# PULLDNx3.net
KiCad netlist of a schematic drawn in Altium Designer
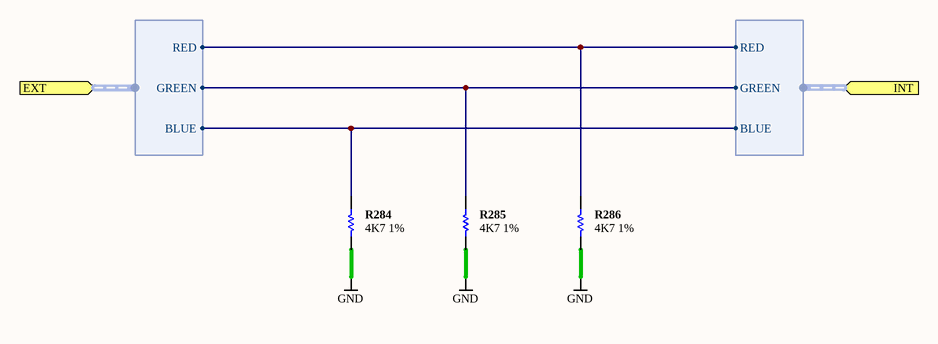
[diagram p0: PULLDNx3.SCHDOC]

(export (version "E")
  (design (tool "Eeschema 10.0.6"))
  (components
    (comp (ref "R284")
      (value "4K7 1%")
      (footprint "RESC1005-STAR")
      (description "Resistor, 4K7 1% 0402 (1005)")
      (fields (field (name "TOLERANCE") "1 %"))
      (libsource (lib "altium-import") (part "root_2_mirrored_RES_"))
    )
    (comp (ref "R285")
      (value "4K7 1%")
      (footprint "RESC1005-STAR")
      (description "Resistor, 4K7 1% 0402 (1005)")
      (fields (field (name "TOLERANCE") "1 %"))
      (libsource (lib "altium-import") (part "root_2_mirrored_RES_"))
    )
    (comp (ref "R286")
      (value "4K7 1%")
      (footprint "RESC1005-STAR")
      (description "Resistor, 4K7 1% 0402 (1005)")
      (fields (field (name "TOLERANCE") "1 %"))
      (libsource (lib "altium-import") (part "root_2_mirrored_RES_"))
    )
  )
  (nets
    (net (code "2") (name "/BLUE") (class "Default")
      (node (ref "R284") (pin "2") (pinfunction "2_2") (pintype "passive"))
    )
    (net (code "3") (name "/GREEN") (class "Default")
      (node (ref "R285") (pin "2") (pinfunction "2_2") (pintype "passive"))
    )
    (net (code "4") (name "/RED") (class "Default")
      (node (ref "R286") (pin "2") (pinfunction "2_2") (pintype "passive"))
    )
    (net (code "6") (name "GND") (class "Default")
      (node (ref "R284") (pin "1") (pinfunction "1_1") (pintype "passive"))
      (node (ref "R285") (pin "1") (pinfunction "1_1") (pintype "passive"))
      (node (ref "R286") (pin "1") (pinfunction "1_1") (pintype "passive"))
    )
  )
)
